# PiDRO1.net
KiCad netlist of a schematic drawn in EAGLE
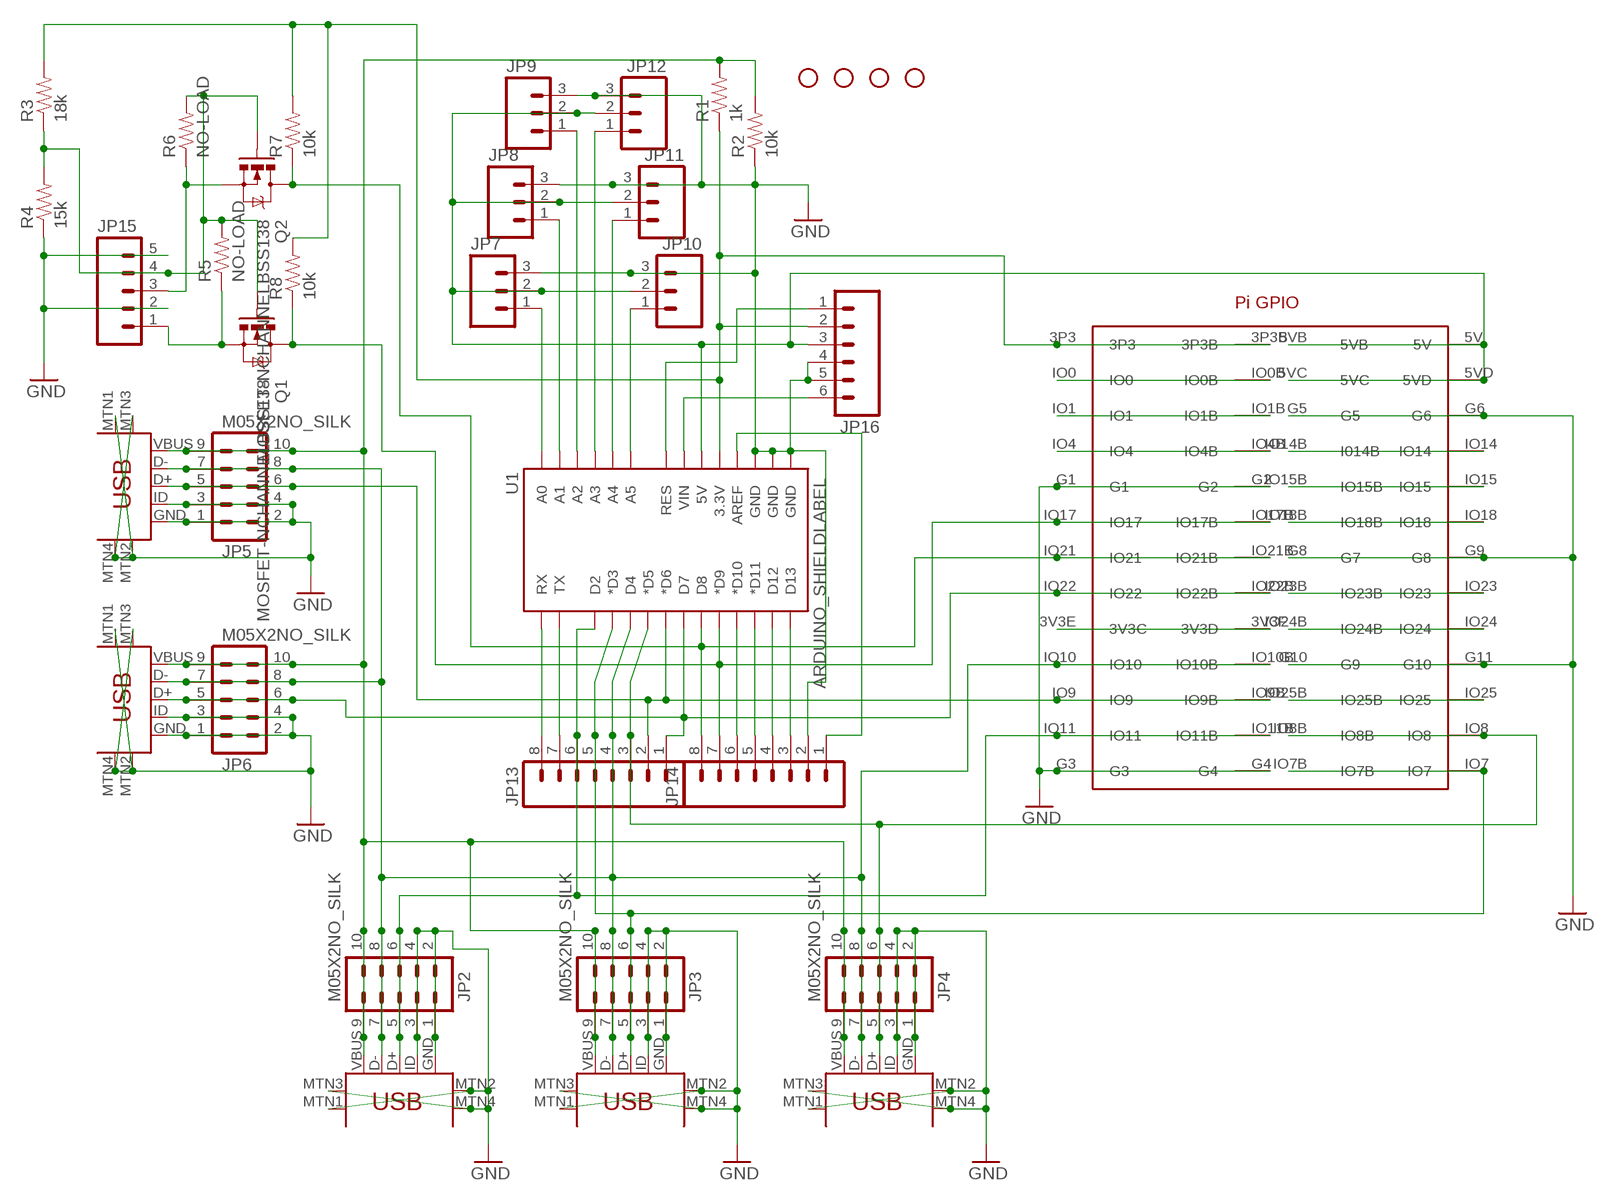
[diagram p0: schematic, sheet 1]

(export (version "E")
  (design (tool "Eeschema 10.0.6"))
  (components
    (comp (ref "JP2")
      (value "M05X2NO_SILK")
      (footprint "eagle-import:2X5_NOSILK")
      (libsource (lib "eagle-import") (part "M05X2NO_SILK"))
    )
    (comp (ref "JP3")
      (value "M05X2NO_SILK")
      (footprint "eagle-import:2X5_NOSILK")
      (libsource (lib "eagle-import") (part "M05X2NO_SILK"))
    )
    (comp (ref "JP4")
      (value "M05X2NO_SILK")
      (footprint "eagle-import:2X5_NOSILK")
      (libsource (lib "eagle-import") (part "M05X2NO_SILK"))
    )
    (comp (ref "JP5")
      (value "M05X2NO_SILK")
      (footprint "eagle-import:2X5_NOSILK")
      (libsource (lib "eagle-import") (part "M05X2NO_SILK"))
    )
    (comp (ref "JP6")
      (value "M05X2NO_SILK")
      (footprint "eagle-import:2X5_NOSILK")
      (libsource (lib "eagle-import") (part "M05X2NO_SILK"))
    )
    (comp (ref "JP7")
      (value "M03LOCK_NO_SILK")
      (footprint "eagle-import:1X03_LOCK_NO_SILK")
      (libsource (lib "eagle-import") (part "M03LOCK_NO_SILK"))
    )
    (comp (ref "JP8")
      (value "M03LOCK_NO_SILK")
      (footprint "eagle-import:1X03_LOCK_NO_SILK")
      (libsource (lib "eagle-import") (part "M03LOCK_NO_SILK"))
    )
    (comp (ref "JP9")
      (value "M03LOCK_NO_SILK")
      (footprint "eagle-import:1X03_LOCK_NO_SILK")
      (libsource (lib "eagle-import") (part "M03LOCK_NO_SILK"))
    )
    (comp (ref "JP10")
      (value "M03LOCK_NO_SILK")
      (footprint "eagle-import:1X03_LOCK_NO_SILK")
      (libsource (lib "eagle-import") (part "M03LOCK_NO_SILK"))
    )
    (comp (ref "JP11")
      (value "M03LOCK_NO_SILK")
      (footprint "eagle-import:1X03_LOCK_NO_SILK")
      (libsource (lib "eagle-import") (part "M03LOCK_NO_SILK"))
    )
    (comp (ref "JP12")
      (value "M03LOCK_NO_SILK")
      (footprint "eagle-import:1X03_LOCK_NO_SILK")
      (libsource (lib "eagle-import") (part "M03LOCK_NO_SILK"))
    )
    (comp (ref "JP13")
      (value "M08")
      (footprint "eagle-import:1X08_PIN1_NO_SILK")
      (libsource (lib "eagle-import") (part "M08"))
    )
    (comp (ref "JP14")
      (value "M08")
      (footprint "eagle-import:1X08_PIN1_NO_SILK")
      (libsource (lib "eagle-import") (part "M08"))
    )
    (comp (ref "JP15")
      (value "M05PTH")
      (footprint "eagle-import:1X05")
      (libsource (lib "eagle-import") (part "M05PTH"))
    )
    (comp (ref "JP16")
      (value "M06LOCK")
      (footprint "eagle-import:1X06_LOCK")
      (libsource (lib "eagle-import") (part "M06LOCK"))
    )
    (comp (ref "Q1")
      (value "MOSFET-NCHANNELBSS138")
      (footprint "eagle-import:SOT23")
      (libsource (lib "eagle-import") (part "MOSFET-NCHANNELBSS138"))
    )
    (comp (ref "Q2")
      (value "MOSFET-NCHANNELBSS138")
      (footprint "eagle-import:SOT23")
      (libsource (lib "eagle-import") (part "MOSFET-NCHANNELBSS138"))
    )
    (comp (ref "R1")
      (value "1k")
      (footprint "eagle-import:0805")
      (libsource (lib "eagle-import") (part "RESISTOR0805-RES"))
    )
    (comp (ref "R2")
      (value "10k")
      (footprint "eagle-import:0805")
      (libsource (lib "eagle-import") (part "RESISTOR0805-RES"))
    )
    (comp (ref "R3")
      (value "18k")
      (footprint "eagle-import:0805")
      (libsource (lib "eagle-import") (part "RESISTOR0805-RES"))
    )
    (comp (ref "R4")
      (value "15k")
      (footprint "eagle-import:0805")
      (libsource (lib "eagle-import") (part "RESISTOR0805-RES"))
    )
    (comp (ref "R5")
      (value "NO-LOAD")
      (footprint "eagle-import:0805")
      (libsource (lib "eagle-import") (part "RESISTOR0805-RES"))
    )
    (comp (ref "R6")
      (value "NO-LOAD")
      (footprint "eagle-import:0805")
      (libsource (lib "eagle-import") (part "RESISTOR0805-RES"))
    )
    (comp (ref "R7")
      (value "10k")
      (footprint "eagle-import:0805")
      (libsource (lib "eagle-import") (part "RESISTOR0805-RES"))
    )
    (comp (ref "R8")
      (value "10k")
      (footprint "eagle-import:0805")
      (libsource (lib "eagle-import") (part "RESISTOR0805-RES"))
    )
    (comp (ref "STANDOFF1")
      (value "STAND-OFF")
      (footprint "eagle-import:STAND-OFF")
      (libsource (lib "eagle-import") (part "STAND-OFF"))
    )
    (comp (ref "STANDOFF2")
      (value "STAND-OFF")
      (footprint "eagle-import:STAND-OFF")
      (libsource (lib "eagle-import") (part "STAND-OFF"))
    )
    (comp (ref "STANDOFF3")
      (value "STAND-OFF")
      (footprint "eagle-import:STAND-OFF")
      (libsource (lib "eagle-import") (part "STAND-OFF"))
    )
    (comp (ref "STANDOFF4")
      (value "STAND-OFF")
      (footprint "eagle-import:STAND-OFF")
      (libsource (lib "eagle-import") (part "STAND-OFF"))
    )
    (comp (ref "U$1")
      (value "PIGPIO_2X")
      (footprint "eagle-import:PI_GPIO_2X")
      (libsource (lib "eagle-import") (part "PIGPIO_2X"))
    )
    (comp (ref "U$2")
      (value "USB-MINIB-5PIN")
      (footprint "eagle-import:USB-MINIB")
      (libsource (lib "eagle-import") (part "USB-MINIB-5PIN"))
    )
    (comp (ref "U$3")
      (value "USB-MINIB-5PIN")
      (footprint "eagle-import:USB-MINIB")
      (libsource (lib "eagle-import") (part "USB-MINIB-5PIN"))
    )
    (comp (ref "U$4")
      (value "USB-MINIB-5PIN")
      (footprint "eagle-import:USB-MINIB")
      (libsource (lib "eagle-import") (part "USB-MINIB-5PIN"))
    )
    (comp (ref "U$5")
      (value "USB-MINIB-5PIN")
      (footprint "eagle-import:USB-MINIB")
      (libsource (lib "eagle-import") (part "USB-MINIB-5PIN"))
    )
    (comp (ref "U$6")
      (value "USB-MINIB-5PIN")
      (footprint "eagle-import:USB-MINIB")
      (libsource (lib "eagle-import") (part "USB-MINIB-5PIN"))
    )
    (comp (ref "U1")
      (value "ARDUINO_SHIELDLABEL")
      (footprint "eagle-import:DUEMILANOVE_SHIELD")
      (libsource (lib "eagle-import") (part "ARDUINO_SHIELDLABEL"))
    )
  )
  (nets
    (net (code "1") (name "GND") (class "Default")
      (node (ref "JP10") (pin "3") (pinfunction "3_3") (pintype "passive"))
      (node (ref "JP11") (pin "3") (pinfunction "3_3") (pintype "passive"))
      (node (ref "JP12") (pin "3") (pinfunction "3_3") (pintype "passive"))
      (node (ref "JP14") (pin "2") (pinfunction "2_2") (pintype "passive"))
      (node (ref "JP15") (pin "2") (pinfunction "2_2") (pintype "passive"))
      (node (ref "JP15") (pin "5") (pinfunction "5_5") (pintype "passive"))
      (node (ref "JP16") (pin "4") (pinfunction "4_4") (pintype "passive"))
      (node (ref "JP16") (pin "5") (pinfunction "5_5") (pintype "passive"))
      (node (ref "JP2") (pin "1") (pinfunction "1_1") (pintype "passive"))
      (node (ref "JP2") (pin "2") (pinfunction "2_2") (pintype "passive"))
      (node (ref "JP2") (pin "3") (pinfunction "3_3") (pintype "passive"))
      (node (ref "JP2") (pin "4") (pinfunction "4_4") (pintype "passive"))
      (node (ref "JP3") (pin "1") (pinfunction "1_1") (pintype "passive"))
      (node (ref "JP3") (pin "2") (pinfunction "2_2") (pintype "passive"))
      (node (ref "JP3") (pin "3") (pinfunction "3_3") (pintype "passive"))
      (node (ref "JP3") (pin "4") (pinfunction "4_4") (pintype "passive"))
      (node (ref "JP4") (pin "1") (pinfunction "1_1") (pintype "passive"))
      (node (ref "JP4") (pin "2") (pinfunction "2_2") (pintype "passive"))
      (node (ref "JP4") (pin "3") (pinfunction "3_3") (pintype "passive"))
      (node (ref "JP4") (pin "4") (pinfunction "4_4") (pintype "passive"))
      (node (ref "JP5") (pin "1") (pinfunction "1_1") (pintype "passive"))
      (node (ref "JP5") (pin "2") (pinfunction "2_2") (pintype "passive"))
      (node (ref "JP5") (pin "3") (pinfunction "3_3") (pintype "passive"))
      (node (ref "JP5") (pin "4") (pinfunction "4_4") (pintype "passive"))
      (node (ref "JP6") (pin "1") (pinfunction "1_1") (pintype "passive"))
      (node (ref "JP6") (pin "2") (pinfunction "2_2") (pintype "passive"))
      (node (ref "JP6") (pin "3") (pinfunction "3_3") (pintype "passive"))
      (node (ref "JP6") (pin "4") (pinfunction "4_4") (pintype "passive"))
      (node (ref "JP7") (pin "3") (pinfunction "3_3") (pintype "passive"))
      (node (ref "JP8") (pin "3") (pinfunction "3_3") (pintype "passive"))
      (node (ref "JP9") (pin "3") (pinfunction "3_3") (pintype "passive"))
      (node (ref "R2") (pin "1") (pinfunction "1_1") (pintype "passive"))
      (node (ref "R4") (pin "1") (pinfunction "1_1") (pintype "passive"))
      (node (ref "U$1") (pin "G1") (pinfunction "G1_G1") (pintype "bidirectional"))
      (node (ref "U$1") (pin "G10") (pinfunction "G9_G10") (pintype "bidirectional"))
      (node (ref "U$1") (pin "G11") (pinfunction "G10_G11") (pintype "bidirectional"))
      (node (ref "U$1") (pin "G2") (pinfunction "G2_G2") (pintype "bidirectional"))
      (node (ref "U$1") (pin "G3") (pinfunction "G3_G3") (pintype "bidirectional"))
      (node (ref "U$1") (pin "G4") (pinfunction "G4_G4") (pintype "bidirectional"))
      (node (ref "U$1") (pin "G5") (pinfunction "G5_G5") (pintype "bidirectional"))
      (node (ref "U$1") (pin "G6") (pinfunction "G6_G6") (pintype "bidirectional"))
      (node (ref "U$1") (pin "G8") (pinfunction "G7_G8") (pintype "bidirectional"))
      (node (ref "U$1") (pin "G9") (pinfunction "G8_G9") (pintype "bidirectional"))
      (node (ref "U$2") (pin "GND") (pinfunction "GND_GND") (pintype "bidirectional"))
      (node (ref "U$2") (pin "ID") (pinfunction "ID_ID") (pintype "bidirectional"))
      (node (ref "U$2") (pin "MTN1") (pinfunction "MTN2_MTN1") (pintype "bidirectional"))
      (node (ref "U$2") (pin "MTN2") (pinfunction "MTN3_MTN2") (pintype "bidirectional"))
      (node (ref "U$2") (pin "MTN3") (pinfunction "MTN1_MTN3") (pintype "bidirectional"))
      (node (ref "U$2") (pin "MTN4") (pinfunction "MTN4_MTN4") (pintype "bidirectional"))
      (node (ref "U$3") (pin "GND") (pinfunction "GND_GND") (pintype "bidirectional"))
      (node (ref "U$3") (pin "ID") (pinfunction "ID_ID") (pintype "bidirectional"))
      (node (ref "U$3") (pin "MTN1") (pinfunction "MTN2_MTN1") (pintype "bidirectional"))
      (node (ref "U$3") (pin "MTN2") (pinfunction "MTN3_MTN2") (pintype "bidirectional"))
      (node (ref "U$3") (pin "MTN3") (pinfunction "MTN1_MTN3") (pintype "bidirectional"))
      (node (ref "U$3") (pin "MTN4") (pinfunction "MTN4_MTN4") (pintype "bidirectional"))
      (node (ref "U$4") (pin "GND") (pinfunction "GND_GND") (pintype "bidirectional"))
      (node (ref "U$4") (pin "ID") (pinfunction "ID_ID") (pintype "bidirectional"))
      (node (ref "U$4") (pin "MTN1") (pinfunction "MTN2_MTN1") (pintype "bidirectional"))
      (node (ref "U$4") (pin "MTN2") (pinfunction "MTN3_MTN2") (pintype "bidirectional"))
      (node (ref "U$4") (pin "MTN3") (pinfunction "MTN1_MTN3") (pintype "bidirectional"))
      (node (ref "U$4") (pin "MTN4") (pinfunction "MTN4_MTN4") (pintype "bidirectional"))
      (node (ref "U$5") (pin "GND") (pinfunction "GND_GND") (pintype "bidirectional"))
      (node (ref "U$5") (pin "ID") (pinfunction "ID_ID") (pintype "bidirectional"))
      (node (ref "U$5") (pin "MTN1") (pinfunction "MTN2_MTN1") (pintype "bidirectional"))
      (node (ref "U$5") (pin "MTN2") (pinfunction "MTN3_MTN2") (pintype "bidirectional"))
      (node (ref "U$5") (pin "MTN3") (pinfunction "MTN1_MTN3") (pintype "bidirectional"))
      (node (ref "U$5") (pin "MTN4") (pinfunction "MTN4_MTN4") (pintype "bidirectional"))
      (node (ref "U$6") (pin "GND") (pinfunction "GND_GND") (pintype "bidirectional"))
      (node (ref "U$6") (pin "ID") (pinfunction "ID_ID") (pintype "bidirectional"))
      (node (ref "U$6") (pin "MTN1") (pinfunction "MTN2_MTN1") (pintype "bidirectional"))
      (node (ref "U$6") (pin "MTN2") (pinfunction "MTN3_MTN2") (pintype "bidirectional"))
      (node (ref "U$6") (pin "MTN3") (pinfunction "MTN1_MTN3") (pintype "bidirectional"))
      (node (ref "U$6") (pin "MTN4") (pinfunction "MTN4_MTN4") (pintype "bidirectional"))
      (node (ref "U1") (pin "GND@0") (pinfunction "GND_GND@0") (pintype "bidirectional"))
      (node (ref "U1") (pin "GND@1") (pinfunction "GND_GND@1") (pintype "bidirectional"))
      (node (ref "U1") (pin "GND@2") (pinfunction "GND_GND@2") (pintype "bidirectional"))
    )
    (net (code "2") (name "Net-(JP2-Pad10)") (class "Default")
      (node (ref "JP2") (pin "10") (pinfunction "10_10") (pintype "passive"))
      (node (ref "JP2") (pin "9") (pinfunction "9_9") (pintype "passive"))
      (node (ref "JP3") (pin "10") (pinfunction "10_10") (pintype "passive"))
      (node (ref "JP3") (pin "9") (pinfunction "9_9") (pintype "passive"))
      (node (ref "JP4") (pin "10") (pinfunction "10_10") (pintype "passive"))
      (node (ref "JP4") (pin "9") (pinfunction "9_9") (pintype "passive"))
      (node (ref "JP5") (pin "10") (pinfunction "10_10") (pintype "passive"))
      (node (ref "JP5") (pin "9") (pinfunction "9_9") (pintype "passive"))
      (node (ref "JP6") (pin "10") (pinfunction "10_10") (pintype "passive"))
      (node (ref "JP6") (pin "9") (pinfunction "9_9") (pintype "passive"))
      (node (ref "R1") (pin "2") (pinfunction "2_2") (pintype "passive"))
      (node (ref "R2") (pin "2") (pinfunction "2_2") (pintype "passive"))
      (node (ref "U$2") (pin "VBUS") (pinfunction "VBUS_VBUS") (pintype "bidirectional"))
      (node (ref "U$3") (pin "VBUS") (pinfunction "VBUS_VBUS") (pintype "bidirectional"))
      (node (ref "U$4") (pin "VBUS") (pinfunction "VBUS_VBUS") (pintype "bidirectional"))
      (node (ref "U$5") (pin "VBUS") (pinfunction "VBUS_VBUS") (pintype "bidirectional"))
      (node (ref "U$6") (pin "VBUS") (pinfunction "VBUS_VBUS") (pintype "bidirectional"))
    )
    (net (code "3") (name "Net-(JP7-Pad1)") (class "Default")
      (node (ref "JP7") (pin "1") (pinfunction "1_1") (pintype "passive"))
      (node (ref "U1") (pin "A0") (pinfunction "A0_A0") (pintype "bidirectional"))
    )
    (net (code "4") (name "Net-(JP8-Pad1)") (class "Default")
      (node (ref "JP8") (pin "1") (pinfunction "1_1") (pintype "passive"))
      (node (ref "U1") (pin "A1") (pinfunction "A1_A1") (pintype "bidirectional"))
    )
    (net (code "5") (name "Net-(JP9-Pad1)") (class "Default")
      (node (ref "JP9") (pin "1") (pinfunction "1_1") (pintype "passive"))
      (node (ref "U1") (pin "A2") (pinfunction "A2_A2") (pintype "bidirectional"))
    )
    (net (code "6") (name "Net-(JP10-Pad1)") (class "Default")
      (node (ref "JP10") (pin "1") (pinfunction "1_1") (pintype "passive"))
      (node (ref "U1") (pin "A5") (pinfunction "A5_A5") (pintype "bidirectional"))
    )
    (net (code "7") (name "Net-(JP10-Pad2)") (class "Default")
      (node (ref "JP10") (pin "2") (pinfunction "2_2") (pintype "passive"))
      (node (ref "JP11") (pin "2") (pinfunction "2_2") (pintype "passive"))
      (node (ref "JP12") (pin "2") (pinfunction "2_2") (pintype "passive"))
      (node (ref "JP16") (pin "3") (pinfunction "3_3") (pintype "passive"))
      (node (ref "JP7") (pin "2") (pinfunction "2_2") (pintype "passive"))
      (node (ref "JP8") (pin "2") (pinfunction "2_2") (pintype "passive"))
      (node (ref "JP9") (pin "2") (pinfunction "2_2") (pintype "passive"))
      (node (ref "U$1") (pin "5V") (pinfunction "5V_5V") (pintype "bidirectional"))
      (node (ref "U$1") (pin "5VB") (pinfunction "5VB_5VB") (pintype "bidirectional"))
      (node (ref "U$1") (pin "5VC") (pinfunction "5VC_5VC") (pintype "bidirectional"))
      (node (ref "U$1") (pin "5VD") (pinfunction "5VD_5VD") (pintype "bidirectional"))
      (node (ref "U1") (pin "5V") (pinfunction "5V_5V") (pintype "bidirectional"))
    )
    (net (code "8") (name "Net-(JP11-Pad1)") (class "Default")
      (node (ref "JP11") (pin "1") (pinfunction "1_1") (pintype "passive"))
      (node (ref "U1") (pin "A4") (pinfunction "A4_A4") (pintype "bidirectional"))
    )
    (net (code "9") (name "Net-(JP12-Pad1)") (class "Default")
      (node (ref "JP12") (pin "1") (pinfunction "1_1") (pintype "passive"))
      (node (ref "U1") (pin "A3") (pinfunction "A3_A3") (pintype "bidirectional"))
    )
    (net (code "10") (name "Net-(JP13-Pad1)") (class "Default")
      (node (ref "JP13") (pin "1") (pinfunction "1_1") (pintype "passive"))
      (node (ref "JP6") (pin "5") (pinfunction "5_5") (pintype "passive"))
      (node (ref "JP6") (pin "6") (pinfunction "6_6") (pintype "passive"))
      (node (ref "U$1") (pin "IO22") (pinfunction "IO22_IO22") (pintype "bidirectional"))
      (node (ref "U$1") (pin "IO22B") (pinfunction "IO22B_IO22B") (pintype "bidirectional"))
      (node (ref "U$6") (pin "D+") (pinfunction "D+_D+") (pintype "bidirectional"))
      (node (ref "U1") (pin "D7") (pinfunction "D7_D7") (pintype "bidirectional"))
    )
    (net (code "11") (name "Net-(JP13-Pad4)") (class "Default")
      (node (ref "JP13") (pin "4") (pinfunction "4_4") (pintype "passive"))
      (node (ref "JP2") (pin "7") (pinfunction "7_7") (pintype "passive"))
      (node (ref "JP2") (pin "8") (pinfunction "8_8") (pintype "passive"))
      (node (ref "JP3") (pin "7") (pinfunction "7_7") (pintype "passive"))
      (node (ref "JP3") (pin "8") (pinfunction "8_8") (pintype "passive"))
      (node (ref "JP4") (pin "7") (pinfunction "7_7") (pintype "passive"))
      (node (ref "JP4") (pin "8") (pinfunction "8_8") (pintype "passive"))
      (node (ref "JP5") (pin "7") (pinfunction "7_7") (pintype "passive"))
      (node (ref "JP5") (pin "8") (pinfunction "8_8") (pintype "passive"))
      (node (ref "JP6") (pin "7") (pinfunction "7_7") (pintype "passive"))
      (node (ref "JP6") (pin "8") (pinfunction "8_8") (pintype "passive"))
      (node (ref "U$1") (pin "IO10") (pinfunction "IO10_IO10") (pintype "bidirectional"))
      (node (ref "U$1") (pin "IO10B") (pinfunction "IO10B_IO10B") (pintype "bidirectional"))
      (node (ref "U$2") (pin "D-") (pinfunction "D-_D-") (pintype "bidirectional"))
      (node (ref "U$3") (pin "D-") (pinfunction "D-_D-") (pintype "bidirectional"))
      (node (ref "U$4") (pin "D-") (pinfunction "D-_D-") (pintype "bidirectional"))
      (node (ref "U$5") (pin "D-") (pinfunction "D-_D-") (pintype "bidirectional"))
      (node (ref "U$6") (pin "D-") (pinfunction "D-_D-") (pintype "bidirectional"))
      (node (ref "U1") (pin "D4") (pinfunction "D4_D4") (pintype "bidirectional"))
    )
    (net (code "12") (name "Net-(JP13-Pad6)") (class "Default")
      (node (ref "JP13") (pin "6") (pinfunction "6_6") (pintype "passive"))
      (node (ref "JP2") (pin "5") (pinfunction "5_5") (pintype "passive"))
      (node (ref "JP2") (pin "6") (pinfunction "6_6") (pintype "passive"))
      (node (ref "U$1") (pin "IO11") (pinfunction "IO11_IO11") (pintype "bidirectional"))
      (node (ref "U$1") (pin "IO11B") (pinfunction "IO11B_IO11B") (pintype "bidirectional"))
      (node (ref "U$2") (pin "D+") (pinfunction "D+_D+") (pintype "bidirectional"))
      (node (ref "U1") (pin "D2") (pinfunction "D2_D2") (pintype "bidirectional"))
    )
    (net (code "13") (name "Net-(JP13-Pad7)") (class "Default")
      (node (ref "JP13") (pin "7") (pinfunction "7_7") (pintype "passive"))
      (node (ref "U1") (pin "TX") (pinfunction "TX_TX") (pintype "bidirectional"))
    )
    (net (code "14") (name "Net-(JP13-Pad8)") (class "Default")
      (node (ref "JP13") (pin "8") (pinfunction "8_8") (pintype "passive"))
      (node (ref "U1") (pin "RX") (pinfunction "RX_RX") (pintype "bidirectional"))
    )
    (net (code "15") (name "Net-(JP14-Pad1)") (class "Default")
      (node (ref "JP14") (pin "1") (pinfunction "1_1") (pintype "passive"))
      (node (ref "U1") (pin "AREF") (pinfunction "AREF_AREF") (pintype "bidirectional"))
    )
    (net (code "16") (name "Net-(JP14-Pad3)") (class "Default")
      (node (ref "JP14") (pin "3") (pinfunction "3_3") (pintype "passive"))
      (node (ref "U1") (pin "D13") (pinfunction "D13_D13") (pintype "bidirectional"))
    )
    (net (code "17") (name "Net-(JP14-Pad4)") (class "Default")
      (node (ref "JP14") (pin "4") (pinfunction "4_4") (pintype "passive"))
      (node (ref "U1") (pin "D12") (pinfunction "D12_D12") (pintype "bidirectional"))
    )
    (net (code "18") (name "Net-(JP16-Pad1)") (class "Default")
      (node (ref "JP16") (pin "1") (pinfunction "1_1") (pintype "passive"))
      (node (ref "U1") (pin "RES") (pinfunction "RES_RES") (pintype "bidirectional"))
    )
    (net (code "19") (name "Net-(JP16-Pad2)") (class "Default")
      (node (ref "JP16") (pin "2") (pinfunction "2_2") (pintype "passive"))
      (node (ref "R1") (pin "1") (pinfunction "1_1") (pintype "passive"))
      (node (ref "R3") (pin "2") (pinfunction "2_2") (pintype "passive"))
      (node (ref "R7") (pin "2") (pinfunction "2_2") (pintype "passive"))
      (node (ref "R8") (pin "2") (pinfunction "2_2") (pintype "passive"))
      (node (ref "U$1") (pin "3P3") (pinfunction "3P3_3P3") (pintype "bidirectional"))
      (node (ref "U$1") (pin "3P3B") (pinfunction "3P3B_3P3B") (pintype "bidirectional"))
      (node (ref "U1") (pin "3.3V") (pinfunction "3.3V_3.3V") (pintype "bidirectional"))
    )
    (net (code "20") (name "Net-(JP16-Pad6)") (class "Default")
      (node (ref "JP16") (pin "6") (pinfunction "6_6") (pintype "passive"))
      (node (ref "U1") (pin "VIN") (pinfunction "VIN_VIN") (pintype "bidirectional"))
    )
    (net (code "21") (name "Net-(Q1-D)") (class "Default")
      (node (ref "JP14") (pin "7") (pinfunction "7_7") (pintype "passive"))
      (node (ref "Q1") (pin "3") (pinfunction "D_3") (pintype "passive"))
      (node (ref "R8") (pin "1") (pinfunction "1_1") (pintype "passive"))
      (node (ref "U$1") (pin "IO17") (pinfunction "IO17_IO17") (pintype "bidirectional"))
      (node (ref "U$1") (pin "IO17B") (pinfunction "IO17B_IO17B") (pintype "bidirectional"))
      (node (ref "U1") (pin "D9") (pinfunction "*D9_D9") (pintype "bidirectional"))
    )
    (net (code "22") (name "Net-(Q1-G)") (class "Default")
      (node (ref "JP15") (pin "4") (pinfunction "4_4") (pintype "passive"))
      (node (ref "Q1") (pin "1") (pinfunction "G_1") (pintype "passive"))
      (node (ref "Q2") (pin "1") (pinfunction "G_1") (pintype "passive"))
      (node (ref "R3") (pin "1") (pinfunction "1_1") (pintype "passive"))
      (node (ref "R4") (pin "2") (pinfunction "2_2") (pintype "passive"))
      (node (ref "R5") (pin "2") (pinfunction "2_2") (pintype "passive"))
      (node (ref "R6") (pin "2") (pinfunction "2_2") (pintype "passive"))
    )
    (net (code "23") (name "Net-(Q1-S)") (class "Default")
      (node (ref "JP15") (pin "1") (pinfunction "1_1") (pintype "passive"))
      (node (ref "Q1") (pin "2") (pinfunction "S_2") (pintype "passive"))
      (node (ref "R5") (pin "1") (pinfunction "1_1") (pintype "passive"))
    )
    (net (code "24") (name "Net-(Q2-D)") (class "Default")
      (node (ref "JP14") (pin "8") (pinfunction "8_8") (pintype "passive"))
      (node (ref "Q2") (pin "3") (pinfunction "D_3") (pintype "passive"))
      (node (ref "R7") (pin "1") (pinfunction "1_1") (pintype "passive"))
      (node (ref "U$1") (pin "IO21") (pinfunction "IO21_IO21") (pintype "bidirectional"))
      (node (ref "U$1") (pin "IO21B") (pinfunction "IO21B_IO21B") (pintype "bidirectional"))
      (node (ref "U1") (pin "D8") (pinfunction "D8_D8") (pintype "bidirectional"))
    )
    (net (code "25") (name "Net-(Q2-S)") (class "Default")
      (node (ref "JP15") (pin "3") (pinfunction "3_3") (pintype "passive"))
      (node (ref "Q2") (pin "2") (pinfunction "S_2") (pintype "passive"))
      (node (ref "R6") (pin "1") (pinfunction "1_1") (pintype "passive"))
    )
    (net (code "26") (name "Net-(U$1-3V3C)") (class "Default")
      (node (ref "U$1") (pin "3V3E") (pinfunction "3V3C_3V3E") (pintype "bidirectional"))
      (node (ref "U$1") (pin "3V3F") (pinfunction "3V3D_3V3F") (pintype "bidirectional"))
    )
    (net (code "27") (name "Net-(U$1-I014B)") (class "Default")
      (node (ref "U$1") (pin "IO14") (pinfunction "IO14_IO14") (pintype "bidirectional"))
      (node (ref "U$1") (pin "IO14B") (pinfunction "I014B_IO14B") (pintype "bidirectional"))
    )
    (net (code "28") (name "Net-(U$1-PadIO0)") (class "Default")
      (node (ref "U$1") (pin "IO0") (pinfunction "IO0_IO0") (pintype "bidirectional"))
      (node (ref "U$1") (pin "IO0B") (pinfunction "IO0B_IO0B") (pintype "bidirectional"))
    )
    (net (code "29") (name "Net-(U$1-PadIO1)") (class "Default")
      (node (ref "U$1") (pin "IO1") (pinfunction "IO1_IO1") (pintype "bidirectional"))
      (node (ref "U$1") (pin "IO1B") (pinfunction "IO1B_IO1B") (pintype "bidirectional"))
    )
    (net (code "30") (name "Net-(U$1-PadIO4)") (class "Default")
      (node (ref "U$1") (pin "IO4") (pinfunction "IO4_IO4") (pintype "bidirectional"))
      (node (ref "U$1") (pin "IO4B") (pinfunction "IO4B_IO4B") (pintype "bidirectional"))
    )
    (net (code "31") (name "Net-(U$1-PadIO15)") (class "Default")
      (node (ref "U$1") (pin "IO15") (pinfunction "IO15_IO15") (pintype "bidirectional"))
      (node (ref "U$1") (pin "IO15B") (pinfunction "IO15B_IO15B") (pintype "bidirectional"))
    )
    (net (code "32") (name "Net-(U$1-PadIO18)") (class "Default")
      (node (ref "U$1") (pin "IO18") (pinfunction "IO18_IO18") (pintype "bidirectional"))
      (node (ref "U$1") (pin "IO18B") (pinfunction "IO18B_IO18B") (pintype "bidirectional"))
    )
    (net (code "33") (name "Net-(U$1-PadIO23)") (class "Default")
      (node (ref "U$1") (pin "IO23") (pinfunction "IO23_IO23") (pintype "bidirectional"))
      (node (ref "U$1") (pin "IO23B") (pinfunction "IO23B_IO23B") (pintype "bidirectional"))
    )
    (net (code "34") (name "Net-(U$1-PadIO24)") (class "Default")
      (node (ref "U$1") (pin "IO24") (pinfunction "IO24_IO24") (pintype "bidirectional"))
      (node (ref "U$1") (pin "IO24B") (pinfunction "IO24B_IO24B") (pintype "bidirectional"))
    )
    (net (code "35") (name "Net-(U$1-PadIO25)") (class "Default")
      (node (ref "U$1") (pin "IO25") (pinfunction "IO25_IO25") (pintype "bidirectional"))
      (node (ref "U$1") (pin "IO25B") (pinfunction "IO25B_IO25B") (pintype "bidirectional"))
    )
    (net (code "36") (name "Net-(U1-*D3)") (class "Default")
      (node (ref "JP13") (pin "5") (pinfunction "5_5") (pintype "passive"))
      (node (ref "JP3") (pin "5") (pinfunction "5_5") (pintype "passive"))
      (node (ref "JP3") (pin "6") (pinfunction "6_6") (pintype "passive"))
      (node (ref "U$1") (pin "IO7") (pinfunction "IO7_IO7") (pintype "bidirectional"))
      (node (ref "U$1") (pin "IO7B") (pinfunction "IO7B_IO7B") (pintype "bidirectional"))
      (node (ref "U$3") (pin "D+") (pinfunction "D+_D+") (pintype "bidirectional"))
      (node (ref "U1") (pin "D3") (pinfunction "*D3_D3") (pintype "bidirectional"))
    )
    (net (code "37") (name "Net-(U1-*D5)") (class "Default")
      (node (ref "JP13") (pin "3") (pinfunction "3_3") (pintype "passive"))
      (node (ref "JP4") (pin "5") (pinfunction "5_5") (pintype "passive"))
      (node (ref "JP4") (pin "6") (pinfunction "6_6") (pintype "passive"))
      (node (ref "U$1") (pin "IO8") (pinfunction "IO8_IO8") (pintype "bidirectional"))
      (node (ref "U$1") (pin "IO8B") (pinfunction "IO8B_IO8B") (pintype "bidirectional"))
      (node (ref "U$4") (pin "D+") (pinfunction "D+_D+") (pintype "bidirectional"))
      (node (ref "U1") (pin "D5") (pinfunction "*D5_D5") (pintype "bidirectional"))
    )
    (net (code "38") (name "Net-(U1-*D6)") (class "Default")
      (node (ref "JP13") (pin "2") (pinfunction "2_2") (pintype "passive"))
      (node (ref "JP5") (pin "5") (pinfunction "5_5") (pintype "passive"))
      (node (ref "JP5") (pin "6") (pinfunction "6_6") (pintype "passive"))
      (node (ref "U$1") (pin "IO9") (pinfunction "IO9_IO9") (pintype "bidirectional"))
      (node (ref "U$1") (pin "IO9B") (pinfunction "IO9B_IO9B") (pintype "bidirectional"))
      (node (ref "U$5") (pin "D+") (pinfunction "D+_D+") (pintype "bidirectional"))
      (node (ref "U1") (pin "D6") (pinfunction "*D6_D6") (pintype "bidirectional"))
    )
    (net (code "39") (name "Net-(U1-*D10)") (class "Default")
      (node (ref "JP14") (pin "6") (pinfunction "6_6") (pintype "passive"))
      (node (ref "U1") (pin "D10") (pinfunction "*D10_D10") (pintype "bidirectional"))
    )
    (net (code "40") (name "Net-(U1-*D11)") (class "Default")
      (node (ref "JP14") (pin "5") (pinfunction "5_5") (pintype "passive"))
      (node (ref "U1") (pin "D11") (pinfunction "*D11_D11") (pintype "bidirectional"))
    )
  )
)
